# snimaci_cast.net
KiCad netlist of a schematic drawn in EAGLE
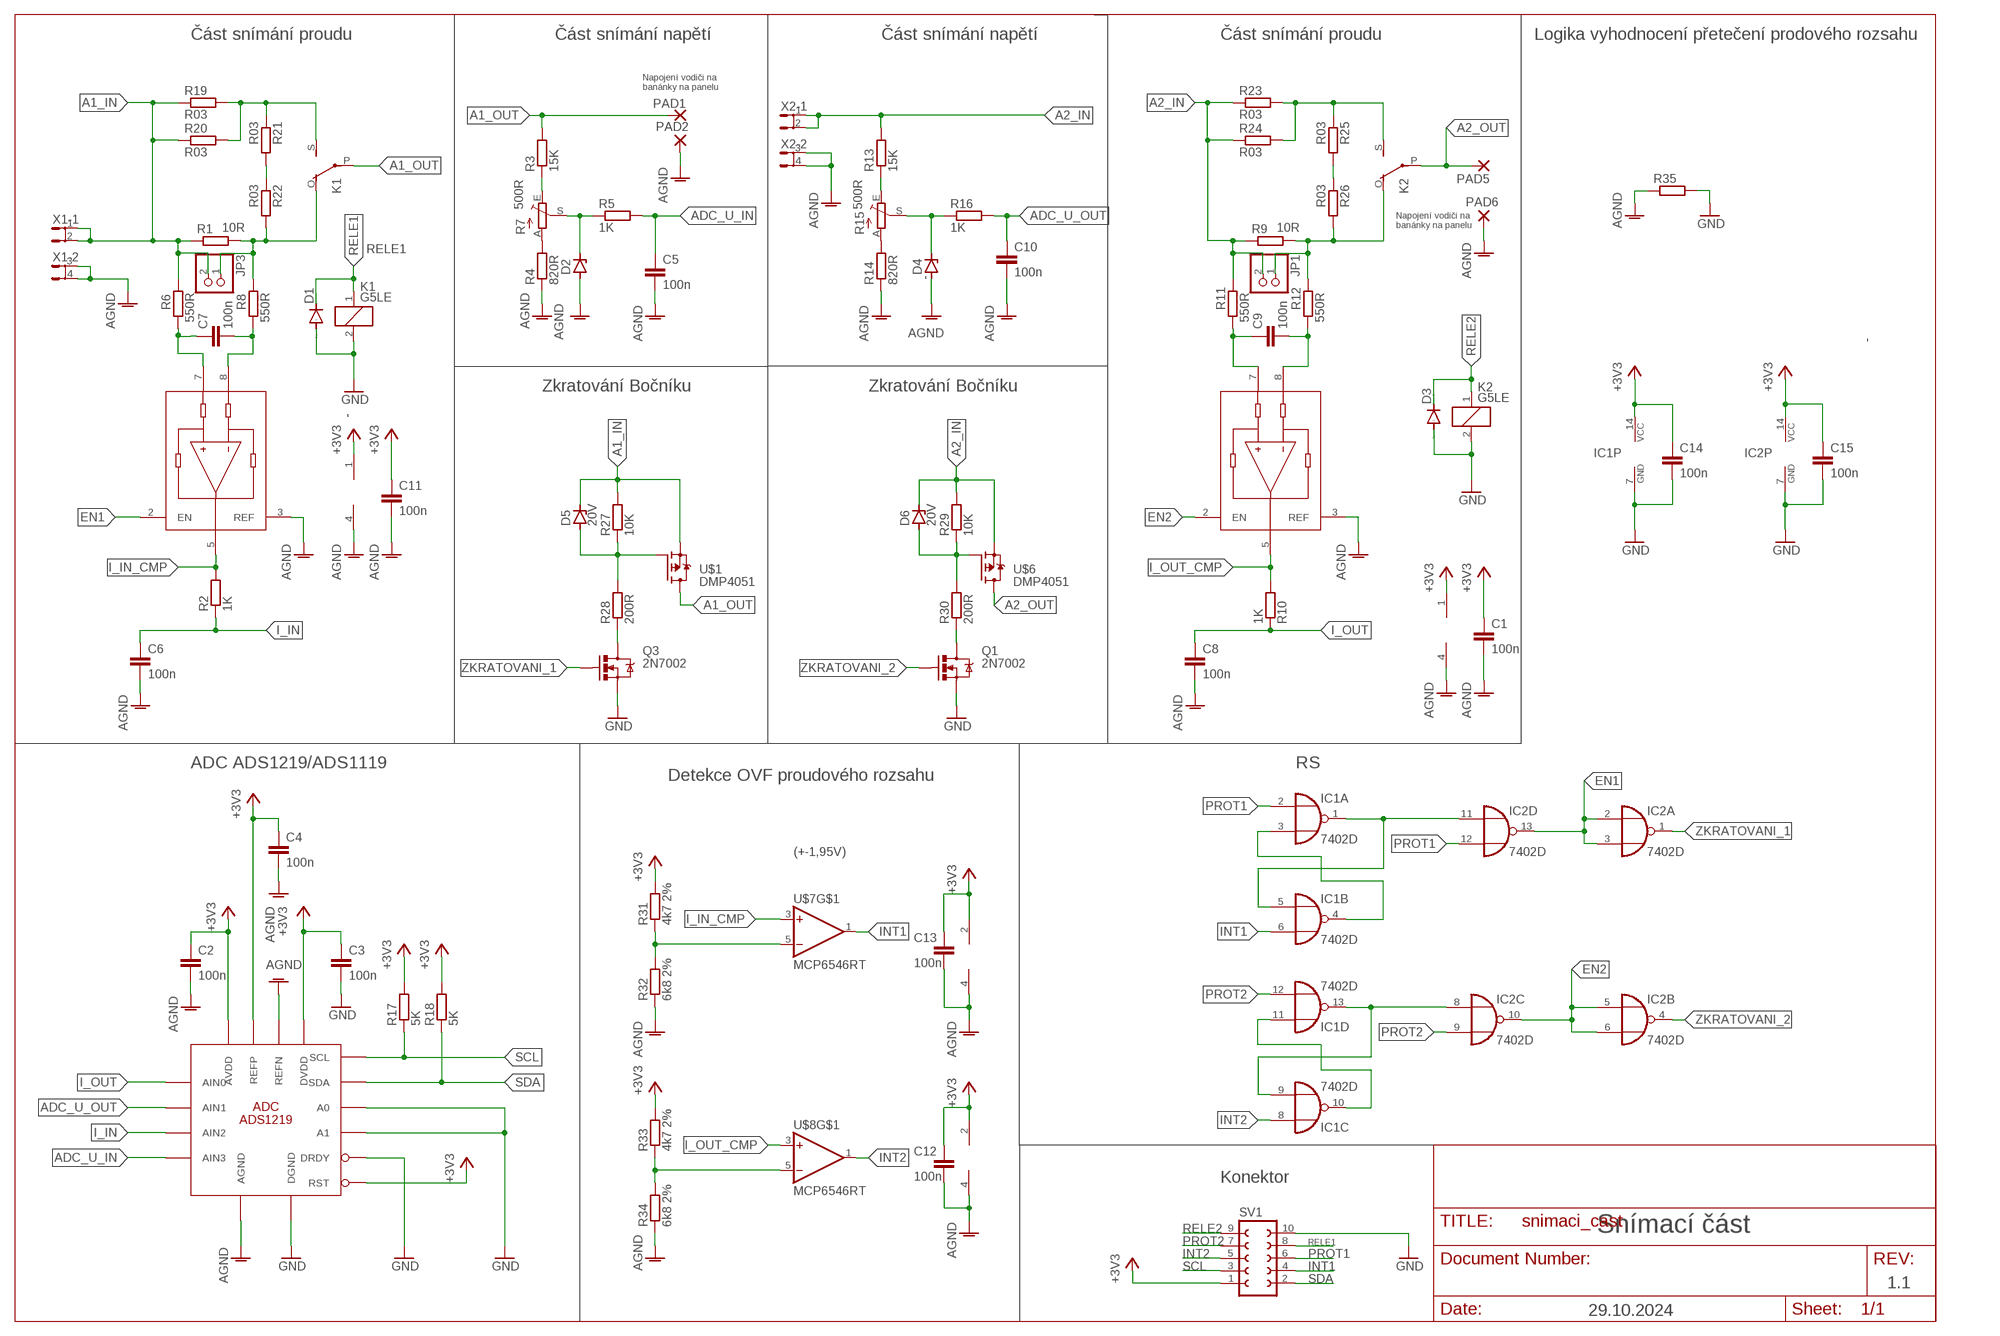
[diagram p0: schematic, sheet 1]

(export (version "E")
  (design (tool "Eeschema 10.0.6"))
  (components
    (comp (ref "C1")
      (value "100n")
      (footprint "eagle-import:C0805")
      (libsource (lib "eagle-import") (part "C-EUC0805"))
    )
    (comp (ref "C2")
      (value "100n")
      (footprint "eagle-import:C0805")
      (libsource (lib "eagle-import") (part "C-EUC0805"))
    )
    (comp (ref "C3")
      (value "100n")
      (footprint "eagle-import:C0805")
      (libsource (lib "eagle-import") (part "C-EUC0805"))
    )
    (comp (ref "C4")
      (value "100n")
      (footprint "eagle-import:C0805")
      (libsource (lib "eagle-import") (part "C-EUC0805"))
    )
    (comp (ref "C5")
      (value "100n")
      (footprint "eagle-import:C0805")
      (libsource (lib "eagle-import") (part "C-EUC0805"))
    )
    (comp (ref "C6")
      (value "100n")
      (footprint "eagle-import:C0805")
      (libsource (lib "eagle-import") (part "C-EUC0805"))
    )
    (comp (ref "C7")
      (value "100n")
      (footprint "eagle-import:C0805")
      (libsource (lib "eagle-import") (part "C-EUC0805"))
    )
    (comp (ref "C8")
      (value "100n")
      (footprint "eagle-import:C0805")
      (libsource (lib "eagle-import") (part "C-EUC0805"))
    )
    (comp (ref "C9")
      (value "100n")
      (footprint "eagle-import:C0805")
      (libsource (lib "eagle-import") (part "C-EUC0805"))
    )
    (comp (ref "C10")
      (value "100n")
      (footprint "eagle-import:C0805")
      (libsource (lib "eagle-import") (part "C-EUC0805"))
    )
    (comp (ref "C11")
      (value "100n")
      (footprint "eagle-import:C0805")
      (libsource (lib "eagle-import") (part "C-EUC0805"))
    )
    (comp (ref "C12")
      (value "100n")
      (footprint "eagle-import:C0805")
      (libsource (lib "eagle-import") (part "C-EUC0805"))
    )
    (comp (ref "C13")
      (value "100n")
      (footprint "eagle-import:C0805")
      (libsource (lib "eagle-import") (part "C-EUC0805"))
    )
    (comp (ref "C14")
      (value "100n")
      (footprint "eagle-import:C0805")
      (libsource (lib "eagle-import") (part "C-EUC0805"))
    )
    (comp (ref "C15")
      (value "100n")
      (footprint "eagle-import:C0805")
      (libsource (lib "eagle-import") (part "C-EUC0805"))
    )
    (comp (ref "D1")
      (value "DIODE-MELF-MLL41")
      (footprint "eagle-import:MELF-MLL41")
      (libsource (lib "eagle-import") (part "DIODE-MELF-MLL41"))
    )
    (comp (ref "D2")
      (value "ZENER-DIODESOD80C")
      (footprint "eagle-import:SOD80C")
      (libsource (lib "eagle-import") (part "ZENER-DIODESOD80C"))
    )
    (comp (ref "D3")
      (value "DIODE-MELF-MLL41")
      (footprint "eagle-import:MELF-MLL41")
      (libsource (lib "eagle-import") (part "DIODE-MELF-MLL41"))
    )
    (comp (ref "D4")
      (value "ZENER-DIODESOD80C")
      (footprint "eagle-import:SOD80C")
      (libsource (lib "eagle-import") (part "ZENER-DIODESOD80C"))
    )
    (comp (ref "D5")
      (value "20V")
      (footprint "eagle-import:SMB")
      (libsource (lib "eagle-import") (part "ZENER-DIODESMB"))
    )
    (comp (ref "D6")
      (value "20V")
      (footprint "eagle-import:SMB")
      (libsource (lib "eagle-import") (part "ZENER-DIODESMB"))
    )
    (comp (ref "IC1")
      (value "7402D")
      (footprint "eagle-import:SO14")
      (libsource (lib "eagle-import") (part "7402D"))
    )
    (comp (ref "IC2")
      (value "7402D")
      (footprint "eagle-import:SO14")
      (libsource (lib "eagle-import") (part "7402D"))
    )
    (comp (ref "JP1")
      (value "PINHD-1X2")
      (footprint "eagle-import:1X02")
      (libsource (lib "eagle-import") (part "PINHD-1X2"))
    )
    (comp (ref "JP3")
      (value "PINHD-1X2")
      (footprint "eagle-import:1X02")
      (libsource (lib "eagle-import") (part "PINHD-1X2"))
    )
    (comp (ref "K1")
      (value "G5LE")
      (footprint "eagle-import:G5LE")
      (libsource (lib "eagle-import") (part "G5LE"))
    )
    (comp (ref "K2")
      (value "G5LE")
      (footprint "eagle-import:G5LE")
      (libsource (lib "eagle-import") (part "G5LE"))
    )
    (comp (ref "PAD1")
      (value "2,15/1,0")
      (footprint "eagle-import:2,15_1,0")
      (libsource (lib "eagle-import") (part "2,15/1,0"))
    )
    (comp (ref "PAD2")
      (value "2,15/1,0")
      (footprint "eagle-import:2,15_1,0")
      (libsource (lib "eagle-import") (part "2,15/1,0"))
    )
    (comp (ref "PAD5")
      (value "2,15/1,0")
      (footprint "eagle-import:2,15_1,0")
      (libsource (lib "eagle-import") (part "2,15/1,0"))
    )
    (comp (ref "PAD6")
      (value "2,15/1,0")
      (footprint "eagle-import:2,15_1,0")
      (libsource (lib "eagle-import") (part "2,15/1,0"))
    )
    (comp (ref "Q1")
      (value "2N7002")
      (footprint "eagle-import:SOT323")
      (libsource (lib "eagle-import") (part "MOSFET-NCHANNEL2N7002PW"))
    )
    (comp (ref "Q3")
      (value "2N7002")
      (footprint "eagle-import:SOT323")
      (libsource (lib "eagle-import") (part "MOSFET-NCHANNEL2N7002PW"))
    )
    (comp (ref "R1")
      (value "10R")
      (footprint "eagle-import:R1206")
      (libsource (lib "eagle-import") (part "R-EU_R1206"))
    )
    (comp (ref "R2")
      (value "1K")
      (footprint "eagle-import:R0805")
      (libsource (lib "eagle-import") (part "R-EU_R0805"))
    )
    (comp (ref "R3")
      (value "15K")
      (footprint "eagle-import:R0805")
      (libsource (lib "eagle-import") (part "R-EU_R0805"))
    )
    (comp (ref "R4")
      (value "820R")
      (footprint "eagle-import:R0805")
      (libsource (lib "eagle-import") (part "R-EU_R0805"))
    )
    (comp (ref "R5")
      (value "1K")
      (footprint "eagle-import:R0805")
      (libsource (lib "eagle-import") (part "R-EU_R0805"))
    )
    (comp (ref "R6")
      (value "550R")
      (footprint "eagle-import:R0805")
      (libsource (lib "eagle-import") (part "R-EU_R0805"))
    )
    (comp (ref "R7")
      (value "500R")
      (footprint "eagle-import:PT-10")
      (libsource (lib "eagle-import") (part "TRIM_EU-PT10"))
    )
    (comp (ref "R8")
      (value "550R")
      (footprint "eagle-import:R0805")
      (libsource (lib "eagle-import") (part "R-EU_R0805"))
    )
    (comp (ref "R9")
      (value "10R")
      (footprint "eagle-import:R1206")
      (libsource (lib "eagle-import") (part "R-EU_R1206"))
    )
    (comp (ref "R10")
      (value "1K")
      (footprint "eagle-import:R0805")
      (libsource (lib "eagle-import") (part "R-EU_R0805"))
    )
    (comp (ref "R11")
      (value "550R")
      (footprint "eagle-import:R0805")
      (libsource (lib "eagle-import") (part "R-EU_R0805"))
    )
    (comp (ref "R12")
      (value "550R")
      (footprint "eagle-import:R0805")
      (libsource (lib "eagle-import") (part "R-EU_R0805"))
    )
    (comp (ref "R13")
      (value "15K")
      (footprint "eagle-import:R0805")
      (libsource (lib "eagle-import") (part "R-EU_R0805"))
    )
    (comp (ref "R14")
      (value "820R")
      (footprint "eagle-import:R0805")
      (libsource (lib "eagle-import") (part "R-EU_R0805"))
    )
    (comp (ref "R15")
      (value "500R")
      (footprint "eagle-import:PT-10")
      (libsource (lib "eagle-import") (part "TRIM_EU-PT10"))
    )
    (comp (ref "R16")
      (value "1K")
      (footprint "eagle-import:R0805")
      (libsource (lib "eagle-import") (part "R-EU_R0805"))
    )
    (comp (ref "R17")
      (value "5K")
      (footprint "eagle-import:R0805")
      (libsource (lib "eagle-import") (part "R-EU_R0805"))
    )
    (comp (ref "R18")
      (value "5K")
      (footprint "eagle-import:R0805")
      (libsource (lib "eagle-import") (part "R-EU_R0805"))
    )
    (comp (ref "R19")
      (value "R03")
      (footprint "eagle-import:R1206")
      (libsource (lib "eagle-import") (part "R-EU_R1206"))
    )
    (comp (ref "R20")
      (value "R03")
      (footprint "eagle-import:R1206")
      (libsource (lib "eagle-import") (part "R-EU_R1206"))
    )
    (comp (ref "R21")
      (value "R03")
      (footprint "eagle-import:R1206")
      (libsource (lib "eagle-import") (part "R-EU_R1206"))
    )
    (comp (ref "R22")
      (value "R03")
      (footprint "eagle-import:R1206")
      (libsource (lib "eagle-import") (part "R-EU_R1206"))
    )
    (comp (ref "R23")
      (value "R03")
      (footprint "eagle-import:R1206")
      (libsource (lib "eagle-import") (part "R-EU_R1206"))
    )
    (comp (ref "R24")
      (value "R03")
      (footprint "eagle-import:R1206")
      (libsource (lib "eagle-import") (part "R-EU_R1206"))
    )
    (comp (ref "R25")
      (value "R03")
      (footprint "eagle-import:R1206")
      (libsource (lib "eagle-import") (part "R-EU_R1206"))
    )
    (comp (ref "R26")
      (value "R03")
      (footprint "eagle-import:R1206")
      (libsource (lib "eagle-import") (part "R-EU_R1206"))
    )
    (comp (ref "R27")
      (value "10K")
      (footprint "eagle-import:R0805")
      (libsource (lib "eagle-import") (part "R-EU_R0805"))
    )
    (comp (ref "R28")
      (value "200R")
      (footprint "eagle-import:R0805")
      (libsource (lib "eagle-import") (part "R-EU_R0805"))
    )
    (comp (ref "R29")
      (value "10K")
      (footprint "eagle-import:R0805")
      (libsource (lib "eagle-import") (part "R-EU_R0805"))
    )
    (comp (ref "R30")
      (value "200R")
      (footprint "eagle-import:R0805")
      (libsource (lib "eagle-import") (part "R-EU_R0805"))
    )
    (comp (ref "R31")
      (value "4k7 2%")
      (footprint "eagle-import:R0805")
      (libsource (lib "eagle-import") (part "R-EU_R0805"))
    )
    (comp (ref "R32")
      (value "6k8 2%")
      (footprint "eagle-import:R0805")
      (libsource (lib "eagle-import") (part "R-EU_R0805"))
    )
    (comp (ref "R33")
      (value "4k7 2%")
      (footprint "eagle-import:R0805")
      (libsource (lib "eagle-import") (part "R-EU_R0805"))
    )
    (comp (ref "R34")
      (value "6k8 2%")
      (footprint "eagle-import:R0805")
      (libsource (lib "eagle-import") (part "R-EU_R0805"))
    )
    (comp (ref "R35")
      (value "R-EU_R0805")
      (footprint "eagle-import:R0805")
      (libsource (lib "eagle-import") (part "R-EU_R0805"))
    )
    (comp (ref "SV1")
      (value "FE05-2")
      (footprint "eagle-import:FE05-2")
      (libsource (lib "eagle-import") (part "FE05-2"))
    )
    (comp (ref "U$1")
      (value "DMP4051")
      (footprint "eagle-import:TO252")
      (libsource (lib "eagle-import") (part "DMP4051"))
    )
    (comp (ref "U$2")
      (value "ADS1219")
      (footprint "eagle-import:TSSOP16")
      (libsource (lib "eagle-import") (part "ADS1219"))
    )
    (comp (ref "U$4")
      (value "INA190")
      (footprint "eagle-import:SOT-23-THIN")
      (libsource (lib "eagle-import") (part "INA190"))
    )
    (comp (ref "U$5")
      (value "INA190")
      (footprint "eagle-import:SOT-23-THIN")
      (libsource (lib "eagle-import") (part "INA190"))
    )
    (comp (ref "U$6")
      (value "DMP4051")
      (footprint "eagle-import:TO252")
      (libsource (lib "eagle-import") (part "DMP4051"))
    )
    (comp (ref "U$7")
      (value "MCP6546RT")
      (footprint "eagle-import:SOT23-5")
      (libsource (lib "eagle-import") (part "MCP6546RT"))
    )
    (comp (ref "U$8")
      (value "MCP6546RT")
      (footprint "eagle-import:SOT23-5")
      (libsource (lib "eagle-import") (part "MCP6546RT"))
    )
    (comp (ref "X1")
      (value "SH5-2")
      (footprint "eagle-import:SH5-2")
      (libsource (lib "eagle-import") (part "SH5-2"))
    )
    (comp (ref "X2")
      (value "SH5-2")
      (footprint "eagle-import:SH5-2")
      (libsource (lib "eagle-import") (part "SH5-2"))
    )
  )
  (nets
    (net (code "1") (name "+3V3") (class "Default")
      (node (ref "C1") (pin "1") (pinfunction "1_1") (pintype "passive"))
      (node (ref "C11") (pin "1") (pinfunction "1_1") (pintype "passive"))
      (node (ref "C12") (pin "1") (pinfunction "1_1") (pintype "passive"))
      (node (ref "C13") (pin "1") (pinfunction "1_1") (pintype "passive"))
      (node (ref "C14") (pin "1") (pinfunction "1_1") (pintype "passive"))
      (node (ref "C15") (pin "1") (pinfunction "1_1") (pintype "passive"))
      (node (ref "C2") (pin "1") (pinfunction "1_1") (pintype "passive"))
      (node (ref "C3") (pin "1") (pinfunction "1_1") (pintype "passive"))
      (node (ref "C4") (pin "1") (pinfunction "1_1") (pintype "passive"))
      (node (ref "IC1") (pin "14") (pinfunction "VCC_14") (pintype "power_in"))
      (node (ref "IC2") (pin "14") (pinfunction "VCC_14") (pintype "power_in"))
      (node (ref "R17") (pin "2") (pinfunction "2_2") (pintype "passive"))
      (node (ref "R18") (pin "2") (pinfunction "2_2") (pintype "passive"))
      (node (ref "R31") (pin "2") (pinfunction "2_2") (pintype "passive"))
      (node (ref "R33") (pin "2") (pinfunction "2_2") (pintype "passive"))
      (node (ref "SV1") (pin "1") (pinfunction "1_1") (pintype "passive"))
      (node (ref "U$2") (pin "12") (pinfunction "AVDD_12") (pintype "power_in"))
      (node (ref "U$2") (pin "13") (pinfunction "DVDD_13") (pintype "power_in"))
      (node (ref "U$2") (pin "3") (pinfunction "RST_3") (pintype "input"))
      (node (ref "U$2") (pin "9") (pinfunction "REFP_9") (pintype "power_in"))
      (node (ref "U$4") (pin "1") (pinfunction "V+_1") (pintype "power_in"))
      (node (ref "U$5") (pin "1") (pinfunction "V+_1") (pintype "power_in"))
      (node (ref "U$7") (pin "2") (pinfunction "V+_2") (pintype "power_in"))
      (node (ref "U$8") (pin "2") (pinfunction "V+_2") (pintype "power_in"))
    )
    (net (code "2") (name "A1_IN") (class "Default")
      (node (ref "D5") (pin "C") (pinfunction "C_C") (pintype "passive"))
      (node (ref "JP3") (pin "2") (pinfunction "2_2") (pintype "passive"))
      (node (ref "R1") (pin "1") (pinfunction "1_1") (pintype "passive"))
      (node (ref "R19") (pin "1") (pinfunction "1_1") (pintype "passive"))
      (node (ref "R20") (pin "1") (pinfunction "1_1") (pintype "passive"))
      (node (ref "R27") (pin "2") (pinfunction "2_2") (pintype "passive"))
      (node (ref "R6") (pin "2") (pinfunction "2_2") (pintype "passive"))
      (node (ref "U$1") (pin "2") (pinfunction "S_2") (pintype "passive"))
      (node (ref "X1") (pin "1") (pinfunction "1_1") (pintype "passive"))
      (node (ref "X1") (pin "2") (pinfunction "2_2") (pintype "passive"))
    )
    (net (code "3") (name "A1_OUT") (class "Default")
      (node (ref "K1") (pin "P") (pinfunction "P_P") (pintype "passive"))
      (node (ref "PAD1") (pin "1") (pinfunction "P_1") (pintype "passive"))
      (node (ref "R3") (pin "2") (pinfunction "2_2") (pintype "passive"))
      (node (ref "U$1") (pin "3") (pinfunction "D_3") (pintype "passive"))
    )
    (net (code "4") (name "A2_IN") (class "Default")
      (node (ref "D6") (pin "C") (pinfunction "C_C") (pintype "passive"))
      (node (ref "JP1") (pin "2") (pinfunction "2_2") (pintype "passive"))
      (node (ref "R11") (pin "2") (pinfunction "2_2") (pintype "passive"))
      (node (ref "R13") (pin "2") (pinfunction "2_2") (pintype "passive"))
      (node (ref "R23") (pin "1") (pinfunction "1_1") (pintype "passive"))
      (node (ref "R24") (pin "1") (pinfunction "1_1") (pintype "passive"))
      (node (ref "R29") (pin "2") (pinfunction "2_2") (pintype "passive"))
      (node (ref "R9") (pin "1") (pinfunction "1_1") (pintype "passive"))
      (node (ref "U$6") (pin "2") (pinfunction "S_2") (pintype "passive"))
      (node (ref "X2") (pin "1") (pinfunction "1_1") (pintype "passive"))
      (node (ref "X2") (pin "2") (pinfunction "2_2") (pintype "passive"))
    )
    (net (code "5") (name "A2_OUT") (class "Default")
      (node (ref "K2") (pin "P") (pinfunction "P_P") (pintype "passive"))
      (node (ref "PAD5") (pin "1") (pinfunction "P_1") (pintype "passive"))
      (node (ref "U$6") (pin "3") (pinfunction "D_3") (pintype "passive"))
    )
    (net (code "6") (name "ADC_U_IN") (class "Default")
      (node (ref "C5") (pin "1") (pinfunction "1_1") (pintype "passive"))
      (node (ref "R5") (pin "2") (pinfunction "2_2") (pintype "passive"))
      (node (ref "U$2") (pin "6") (pinfunction "AIN3_6") (pintype "input"))
    )
    (net (code "7") (name "ADC_U_OUT") (class "Default")
      (node (ref "C10") (pin "1") (pinfunction "1_1") (pintype "passive"))
      (node (ref "R16") (pin "2") (pinfunction "2_2") (pintype "passive"))
      (node (ref "U$2") (pin "10") (pinfunction "AIN1_10") (pintype "input"))
    )
    (net (code "8") (name "AGND") (class "Default")
      (node (ref "C1") (pin "2") (pinfunction "2_2") (pintype "passive"))
      (node (ref "C10") (pin "2") (pinfunction "2_2") (pintype "passive"))
      (node (ref "C11") (pin "2") (pinfunction "2_2") (pintype "passive"))
      (node (ref "C12") (pin "2") (pinfunction "2_2") (pintype "passive"))
      (node (ref "C13") (pin "2") (pinfunction "2_2") (pintype "passive"))
      (node (ref "C2") (pin "2") (pinfunction "2_2") (pintype "passive"))
      (node (ref "C4") (pin "2") (pinfunction "2_2") (pintype "passive"))
      (node (ref "C5") (pin "2") (pinfunction "2_2") (pintype "passive"))
      (node (ref "C6") (pin "2") (pinfunction "2_2") (pintype "passive"))
      (node (ref "C8") (pin "2") (pinfunction "2_2") (pintype "passive"))
      (node (ref "D2") (pin "A") (pinfunction "A_A") (pintype "passive"))
      (node (ref "D4") (pin "A") (pinfunction "A_A") (pintype "passive"))
      (node (ref "PAD2") (pin "1") (pinfunction "P_1") (pintype "passive"))
      (node (ref "PAD6") (pin "1") (pinfunction "P_1") (pintype "passive"))
      (node (ref "R14") (pin "1") (pinfunction "1_1") (pintype "passive"))
      (node (ref "R32") (pin "1") (pinfunction "1_1") (pintype "passive"))
      (node (ref "R34") (pin "1") (pinfunction "1_1") (pintype "passive"))
      (node (ref "R35") (pin "1") (pinfunction "1_1") (pintype "passive"))
      (node (ref "R4") (pin "1") (pinfunction "1_1") (pintype "passive"))
      (node (ref "U$2") (pin "5") (pinfunction "AGND_5") (pintype "power_in"))
      (node (ref "U$2") (pin "8") (pinfunction "REFN_8") (pintype "power_in"))
      (node (ref "U$4") (pin "3") (pinfunction "REF_3") (pintype "input"))
      (node (ref "U$4") (pin "4") (pinfunction "V-_4") (pintype "power_in"))
      (node (ref "U$5") (pin "3") (pinfunction "REF_3") (pintype "input"))
      (node (ref "U$5") (pin "4") (pinfunction "V-_4") (pintype "power_in"))
      (node (ref "U$7") (pin "4") (pinfunction "V-_4") (pintype "power_in"))
      (node (ref "U$8") (pin "4") (pinfunction "V-_4") (pintype "power_in"))
      (node (ref "X1") (pin "3") (pinfunction "1_3") (pintype "passive"))
      (node (ref "X1") (pin "4") (pinfunction "2_4") (pintype "passive"))
      (node (ref "X2") (pin "3") (pinfunction "1_3") (pintype "passive"))
      (node (ref "X2") (pin "4") (pinfunction "2_4") (pintype "passive"))
    )
    (net (code "9") (name "EN1") (class "Default")
      (node (ref "IC2") (pin "13") (pinfunction "O_13") (pintype "output"))
      (node (ref "IC2") (pin "2") (pinfunction "I0_2") (pintype "input"))
      (node (ref "IC2") (pin "3") (pinfunction "I1_3") (pintype "input"))
      (node (ref "U$4") (pin "2") (pinfunction "EN_2") (pintype "input"))
    )
    (net (code "10") (name "EN2") (class "Default")
      (node (ref "IC2") (pin "10") (pinfunction "O_10") (pintype "output"))
      (node (ref "IC2") (pin "5") (pinfunction "I0_5") (pintype "input"))
      (node (ref "IC2") (pin "6") (pinfunction "I1_6") (pintype "input"))
      (node (ref "U$5") (pin "2") (pinfunction "EN_2") (pintype "input"))
    )
    (net (code "11") (name "GND") (class "Default")
      (node (ref "C14") (pin "2") (pinfunction "2_2") (pintype "passive"))
      (node (ref "C15") (pin "2") (pinfunction "2_2") (pintype "passive"))
      (node (ref "C3") (pin "2") (pinfunction "2_2") (pintype "passive"))
      (node (ref "D1") (pin "A") (pinfunction "A_A") (pintype "passive"))
      (node (ref "D3") (pin "A") (pinfunction "A_A") (pintype "passive"))
      (node (ref "IC1") (pin "7") (pinfunction "GND_7") (pintype "power_in"))
      (node (ref "IC2") (pin "7") (pinfunction "GND_7") (pintype "power_in"))
      (node (ref "K1") (pin "2") (pinfunction "2_2") (pintype "passive"))
      (node (ref "K2") (pin "2") (pinfunction "2_2") (pintype "passive"))
      (node (ref "Q1") (pin "2") (pinfunction "S_2") (pintype "passive"))
      (node (ref "Q3") (pin "2") (pinfunction "S_2") (pintype "passive"))
      (node (ref "R35") (pin "2") (pinfunction "2_2") (pintype "passive"))
      (node (ref "SV1") (pin "10") (pinfunction "10_10") (pintype "passive"))
      (node (ref "U$2") (pin "1") (pinfunction "A0_1") (pintype "input"))
      (node (ref "U$2") (pin "14") (pinfunction "DRDY_14") (pintype "output"))
      (node (ref "U$2") (pin "2") (pinfunction "A1_2") (pintype "input"))
      (node (ref "U$2") (pin "4") (pinfunction "DGND_4") (pintype "power_in"))
    )
    (net (code "12") (name "INT1") (class "Default")
      (node (ref "IC1") (pin "6") (pinfunction "I1_6") (pintype "input"))
      (node (ref "SV1") (pin "4") (pinfunction "4_4") (pintype "passive"))
      (node (ref "U$7") (pin "1") (pinfunction "OUT_1") (pintype "output"))
    )
    (net (code "13") (name "INT2") (class "Default")
      (node (ref "IC1") (pin "8") (pinfunction "I0_8") (pintype "input"))
      (node (ref "SV1") (pin "5") (pinfunction "5_5") (pintype "passive"))
      (node (ref "U$8") (pin "1") (pinfunction "OUT_1") (pintype "output"))
    )
    (net (code "14") (name "I_IN") (class "Default")
      (node (ref "C6") (pin "1") (pinfunction "1_1") (pintype "passive"))
      (node (ref "R2") (pin "1") (pinfunction "1_1") (pintype "passive"))
      (node (ref "U$2") (pin "7") (pinfunction "AIN2_7") (pintype "input"))
    )
    (net (code "15") (name "I_IN_CMP") (class "Default")
      (node (ref "R2") (pin "2") (pinfunction "2_2") (pintype "passive"))
      (node (ref "U$4") (pin "5") (pinfunction "P$4_5") (pintype "output"))
      (node (ref "U$7") (pin "3") (pinfunction "+IN_3") (pintype "input"))
    )
    (net (code "16") (name "I_OUT") (class "Default")
      (node (ref "C8") (pin "1") (pinfunction "1_1") (pintype "passive"))
      (node (ref "R10") (pin "1") (pinfunction "1_1") (pintype "passive"))
      (node (ref "U$2") (pin "11") (pinfunction "AIN0_11") (pintype "input"))
    )
    (net (code "17") (name "I_OUT_CMP") (class "Default")
      (node (ref "R10") (pin "2") (pinfunction "2_2") (pintype "passive"))
      (node (ref "U$5") (pin "5") (pinfunction "P$4_5") (pintype "output"))
      (node (ref "U$8") (pin "3") (pinfunction "+IN_3") (pintype "input"))
    )
    (net (code "18") (name "Net-(D2-PadC)") (class "Default")
      (node (ref "D2") (pin "C") (pinfunction "C_C") (pintype "passive"))
      (node (ref "R5") (pin "1") (pinfunction "1_1") (pintype "passive"))
      (node (ref "R7") (pin "S") (pinfunction "S_S") (pintype "passive"))
    )
    (net (code "19") (name "Net-(D4-PadC)") (class "Default")
      (node (ref "D4") (pin "C") (pinfunction "C_C") (pintype "passive"))
      (node (ref "R15") (pin "S") (pinfunction "S_S") (pintype "passive"))
      (node (ref "R16") (pin "1") (pinfunction "1_1") (pintype "passive"))
    )
    (net (code "20") (name "Net-(IC1A-I1)") (class "Default")
      (node (ref "IC1") (pin "3") (pinfunction "I1_3") (pintype "input"))
      (node (ref "IC1") (pin "4") (pinfunction "O_4") (pintype "output"))
    )
    (net (code "21") (name "Net-(IC1A-O)") (class "Default")
      (node (ref "IC1") (pin "1") (pinfunction "O_1") (pintype "output"))
      (node (ref "IC1") (pin "5") (pinfunction "I0_5") (pintype "input"))
      (node (ref "IC2") (pin "11") (pinfunction "I0_11") (pintype "input"))
    )
    (net (code "22") (name "Net-(IC1C-I1)") (class "Default")
      (node (ref "IC1") (pin "13") (pinfunction "O_13") (pintype "output"))
      (node (ref "IC1") (pin "9") (pinfunction "I1_9") (pintype "input"))
      (node (ref "IC2") (pin "8") (pinfunction "I0_8") (pintype "input"))
    )
    (net (code "23") (name "Net-(IC1C-O)") (class "Default")
      (node (ref "IC1") (pin "10") (pinfunction "O_10") (pintype "output"))
      (node (ref "IC1") (pin "11") (pinfunction "I0_11") (pintype "input"))
    )
    (net (code "24") (name "Net-(JP1-Pad1)") (class "Default")
      (node (ref "JP1") (pin "1") (pinfunction "1_1") (pintype "passive"))
      (node (ref "K2") (pin "O") (pinfunction "O_O") (pintype "passive"))
      (node (ref "R12") (pin "2") (pinfunction "2_2") (pintype "passive"))
      (node (ref "R26") (pin "2") (pinfunction "2_2") (pintype "passive"))
      (node (ref "R9") (pin "2") (pinfunction "2_2") (pintype "passive"))
    )
    (net (code "25") (name "Net-(JP3-Pad1)") (class "Default")
      (node (ref "JP3") (pin "1") (pinfunction "1_1") (pintype "passive"))
      (node (ref "K1") (pin "O") (pinfunction "O_O") (pintype "passive"))
      (node (ref "R1") (pin "2") (pinfunction "2_2") (pintype "passive"))
      (node (ref "R22") (pin "2") (pinfunction "2_2") (pintype "passive"))
      (node (ref "R8") (pin "2") (pinfunction "2_2") (pintype "passive"))
    )
    (net (code "26") (name "Net-(K1-PadS)") (class "Default")
      (node (ref "K1") (pin "S") (pinfunction "S_S") (pintype "passive"))
      (node (ref "R19") (pin "2") (pinfunction "2_2") (pintype "passive"))
      (node (ref "R20") (pin "2") (pinfunction "2_2") (pintype "passive"))
      (node (ref "R21") (pin "1") (pinfunction "1_1") (pintype "passive"))
    )
    (net (code "27") (name "Net-(K2-PadS)") (class "Default")
      (node (ref "K2") (pin "S") (pinfunction "S_S") (pintype "passive"))
      (node (ref "R23") (pin "2") (pinfunction "2_2") (pintype "passive"))
      (node (ref "R24") (pin "2") (pinfunction "2_2") (pintype "passive"))
      (node (ref "R25") (pin "1") (pinfunction "1_1") (pintype "passive"))
    )
    (net (code "28") (name "Net-(Q1-D)") (class "Default")
      (node (ref "Q1") (pin "3") (pinfunction "D_3") (pintype "passive"))
      (node (ref "R30") (pin "1") (pinfunction "1_1") (pintype "passive"))
    )
    (net (code "29") (name "Net-(Q3-D)") (class "Default")
      (node (ref "Q3") (pin "3") (pinfunction "D_3") (pintype "passive"))
      (node (ref "R28") (pin "1") (pinfunction "1_1") (pintype "passive"))
    )
    (net (code "30") (name "Net-(R3-Pad1)") (class "Default")
      (node (ref "R3") (pin "1") (pinfunction "1_1") (pintype "passive"))
      (node (ref "R7") (pin "E") (pinfunction "E_E") (pintype "passive"))
    )
    (net (code "31") (name "Net-(R4-Pad2)") (class "Default")
      (node (ref "R4") (pin "2") (pinfunction "2_2") (pintype "passive"))
      (node (ref "R7") (pin "A") (pinfunction "A_A") (pintype "passive"))
    )
    (net (code "32") (name "Net-(R13-Pad1)") (class "Default")
      (node (ref "R13") (pin "1") (pinfunction "1_1") (pintype "passive"))
      (node (ref "R15") (pin "E") (pinfunction "E_E") (pintype "passive"))
    )
    (net (code "33") (name "Net-(R14-Pad2)") (class "Default")
      (node (ref "R14") (pin "2") (pinfunction "2_2") (pintype "passive"))
      (node (ref "R15") (pin "A") (pinfunction "A_A") (pintype "passive"))
    )
    (net (code "34") (name "Net-(R21-Pad2)") (class "Default")
      (node (ref "R21") (pin "2") (pinfunction "2_2") (pintype "passive"))
      (node (ref "R22") (pin "1") (pinfunction "1_1") (pintype "passive"))
    )
    (net (code "35") (name "Net-(R25-Pad2)") (class "Default")
      (node (ref "R25") (pin "2") (pinfunction "2_2") (pintype "passive"))
      (node (ref "R26") (pin "1") (pinfunction "1_1") (pintype "passive"))
    )
    (net (code "36") (name "Net-(U$1-G)") (class "Default")
      (node (ref "D5") (pin "A") (pinfunction "A_A") (pintype "passive"))
      (node (ref "R27") (pin "1") (pinfunction "1_1") (pintype "passive"))
      (node (ref "R28") (pin "2") (pinfunction "2_2") (pintype "passive"))
      (node (ref "U$1") (pin "1") (pinfunction "G_1") (pintype "passive"))
    )
    (net (code "37") (name "Net-(U$4A-+)") (class "Default")
      (node (ref "C7") (pin "1") (pinfunction "1_1") (pintype "passive"))
      (node (ref "R6") (pin "1") (pinfunction "1_1") (pintype "passive"))
      (node (ref "U$4") (pin "7") (pinfunction "+_7") (pintype "input"))
    )
    (net (code "38") (name "Net-(U$4A--)") (class "Default")
      (node (ref "C7") (pin "2") (pinfunction "2_2") (pintype "passive"))
      (node (ref "R8") (pin "1") (pinfunction "1_1") (pintype "passive"))
      (node (ref "U$4") (pin "8") (pinfunction "-_8") (pintype "input"))
    )
    (net (code "39") (name "Net-(U$5A-+)") (class "Default")
      (node (ref "C9") (pin "1") (pinfunction "1_1") (pintype "passive"))
      (node (ref "R11") (pin "1") (pinfunction "1_1") (pintype "passive"))
      (node (ref "U$5") (pin "7") (pinfunction "+_7") (pintype "input"))
    )
    (net (code "40") (name "Net-(U$5A--)") (class "Default")
      (node (ref "C9") (pin "2") (pinfunction "2_2") (pintype "passive"))
      (node (ref "R12") (pin "1") (pinfunction "1_1") (pintype "passive"))
      (node (ref "U$5") (pin "8") (pinfunction "-_8") (pintype "input"))
    )
    (net (code "41") (name "Net-(U$6-G)") (class "Default")
      (node (ref "D6") (pin "A") (pinfunction "A_A") (pintype "passive"))
      (node (ref "R29") (pin "1") (pinfunction "1_1") (pintype "passive"))
      (node (ref "R30") (pin "2") (pinfunction "2_2") (pintype "passive"))
      (node (ref "U$6") (pin "1") (pinfunction "G_1") (pintype "passive"))
    )
    (net (code "42") (name "Net-(U$7A--IN)") (class "Default")
      (node (ref "R31") (pin "1") (pinfunction "1_1") (pintype "passive"))
      (node (ref "R32") (pin "2") (pinfunction "2_2") (pintype "passive"))
      (node (ref "U$7") (pin "5") (pinfunction "-IN_5") (pintype "input"))
    )
    (net (code "43") (name "Net-(U$8A--IN)") (class "Default")
      (node (ref "R33") (pin "1") (pinfunction "1_1") (pintype "passive"))
      (node (ref "R34") (pin "2") (pinfunction "2_2") (pintype "passive"))
      (node (ref "U$8") (pin "5") (pinfunction "-IN_5") (pintype "input"))
    )
    (net (code "44") (name "PROT1") (class "Default")
      (node (ref "IC1") (pin "2") (pinfunction "I0_2") (pintype "input"))
      (node (ref "IC2") (pin "12") (pinfunction "I1_12") (pintype "input"))
      (node (ref "SV1") (pin "6") (pinfunction "6_6") (pintype "passive"))
    )
    (net (code "45") (name "PROT2") (class "Default")
      (node (ref "IC1") (pin "12") (pinfunction "I1_12") (pintype "input"))
      (node (ref "IC2") (pin "9") (pinfunction "I1_9") (pintype "input"))
      (node (ref "SV1") (pin "7") (pinfunction "7_7") (pintype "passive"))
    )
    (net (code "46") (name "RELE1") (class "Default")
      (node (ref "D1") (pin "C") (pinfunction "C_C") (pintype "passive"))
      (node (ref "K1") (pin "1") (pinfunction "1_1") (pintype "passive"))
      (node (ref "SV1") (pin "8") (pinfunction "8_8") (pintype "passive"))
    )
    (net (code "47") (name "RELE2") (class "Default")
      (node (ref "D3") (pin "C") (pinfunction "C_C") (pintype "passive"))
      (node (ref "K2") (pin "1") (pinfunction "1_1") (pintype "passive"))
      (node (ref "SV1") (pin "9") (pinfunction "9_9") (pintype "passive"))
    )
    (net (code "48") (name "SCL") (class "Default")
      (node (ref "R17") (pin "1") (pinfunction "1_1") (pintype "passive"))
      (node (ref "SV1") (pin "3") (pinfunction "3_3") (pintype "passive"))
      (node (ref "U$2") (pin "16") (pinfunction "SCL_16") (pintype "bidirectional"))
    )
    (net (code "49") (name "SDA") (class "Default")
      (node (ref "R18") (pin "1") (pinfunction "1_1") (pintype "passive"))
      (node (ref "SV1") (pin "2") (pinfunction "2_2") (pintype "passive"))
      (node (ref "U$2") (pin "15") (pinfunction "SDA_15") (pintype "bidirectional"))
    )
    (net (code "50") (name "ZKRATOVANI_1") (class "Default")
      (node (ref "IC2") (pin "1") (pinfunction "O_1") (pintype "output"))
      (node (ref "Q3") (pin "1") (pinfunction "G_1") (pintype "passive"))
    )
    (net (code "51") (name "ZKRATOVANI_2") (class "Default")
      (node (ref "IC2") (pin "4") (pinfunction "O_4") (pintype "output"))
      (node (ref "Q1") (pin "1") (pinfunction "G_1") (pintype "passive"))
    )
  )
)
